# Beacon.net
KiCad netlist of a schematic drawn in EAGLE
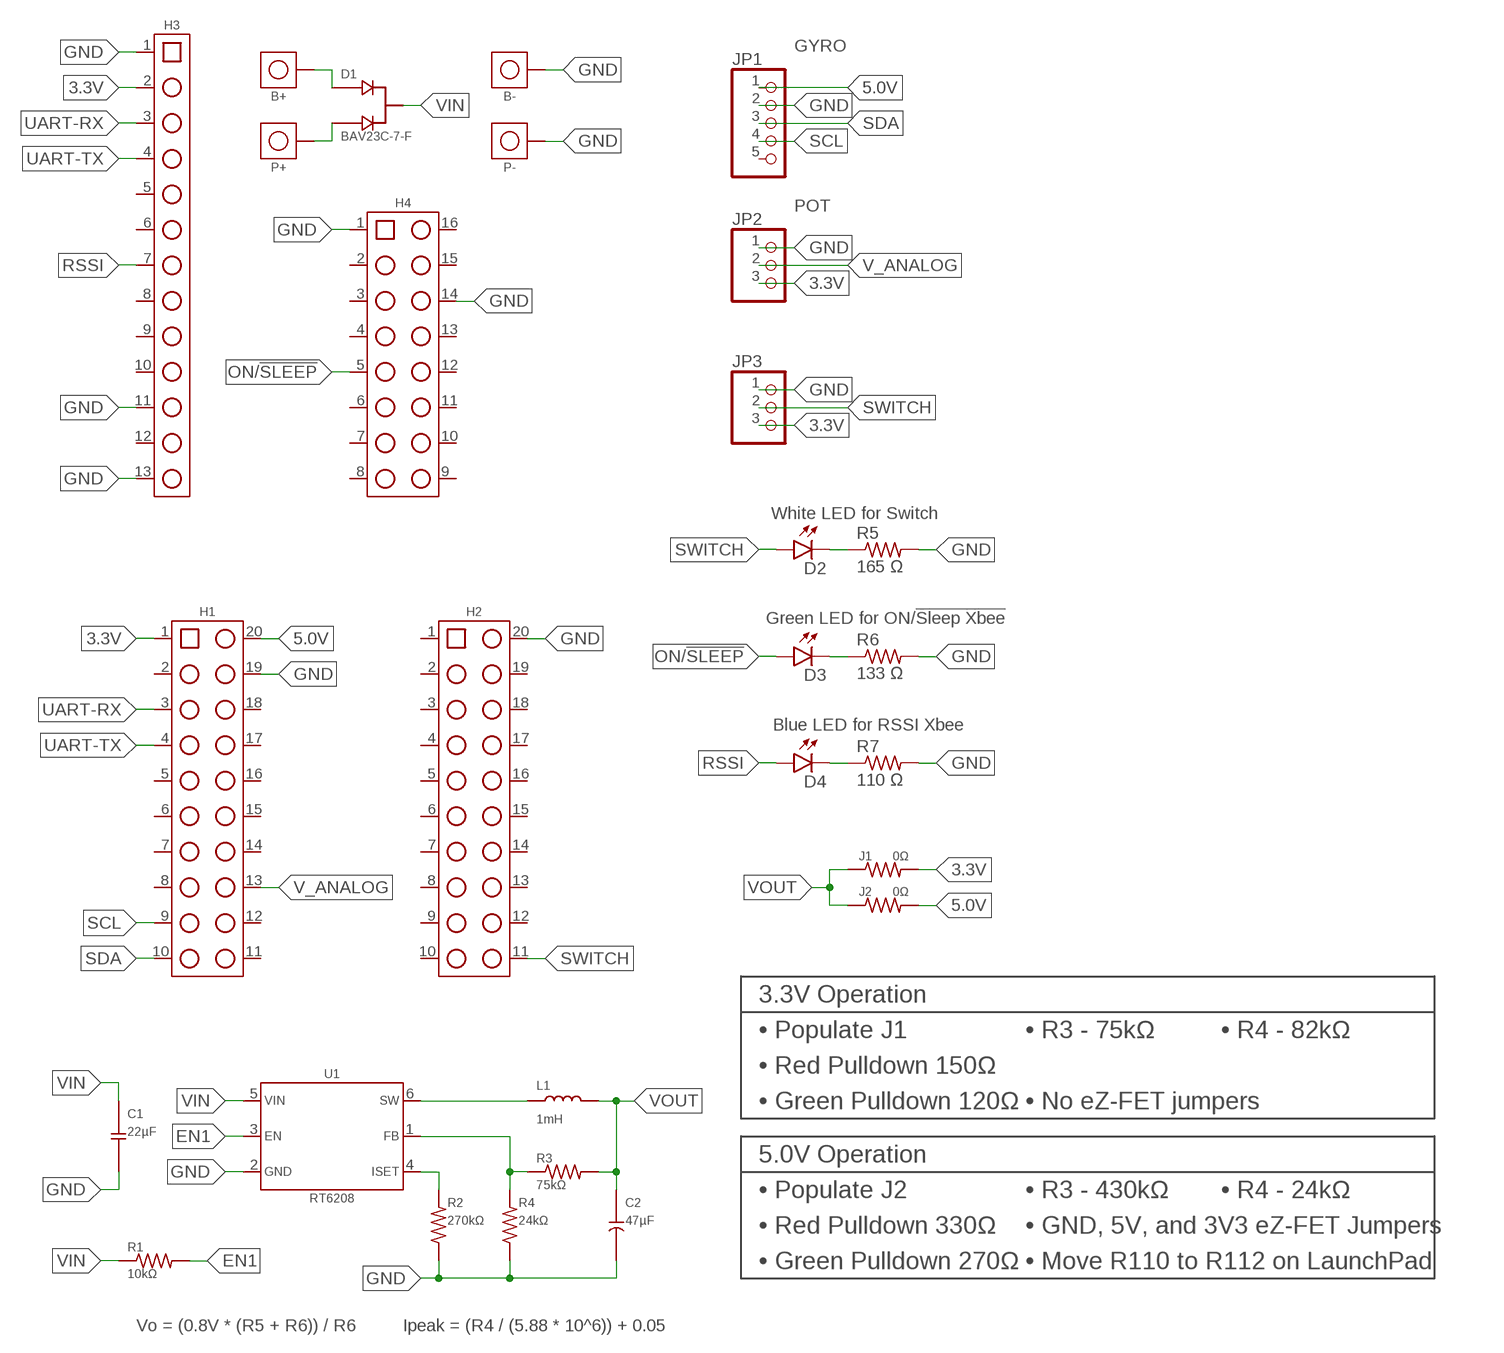
[diagram p0: schematic, sheet 1]

(export (version "E")
  (design (tool "Eeschema 10.0.6"))
  (components
    (comp (ref "B+")
      (value "CON_HEADER-01WTB-24G")
      (footprint "eagle-import:THT_WTB-24G")
      (libsource (lib "eagle-import") (part "CON_HEADER-01WTB-24G"))
    )
    (comp (ref "B-")
      (value "CON_HEADER-01WTB-24G")
      (footprint "eagle-import:THT_WTB-24G")
      (libsource (lib "eagle-import") (part "CON_HEADER-01WTB-24G"))
    )
    (comp (ref "C1")
      (value "22µF")
      (footprint "eagle-import:SMT_1206")
      (libsource (lib "eagle-import") (part "PAS_C1206"))
    )
    (comp (ref "C2")
      (value "47µF")
      (footprint "eagle-import:SMT_CAP-1206")
      (libsource (lib "eagle-import") (part "PAS_C-POLAR"))
    )
    (comp (ref "D1")
      (value "BAV23C-7-F")
      (footprint "eagle-import:SMT_SOT23-3")
      (libsource (lib "eagle-import") (part "SEM_DIODE-PAIR-CC"))
    )
    (comp (ref "D2")
      (value "BEAGLEBONE_BLUE_LED-FKIT-1206")
      (footprint "eagle-import:BEAGLEBONE_BLUE_BEAGLEBONE_BLUE_FKIT-LED-1206")
      (libsource (lib "eagle-import") (part "BEAGLEBONE_BLUE_LED-FKIT-1206"))
    )
    (comp (ref "D3")
      (value "BEAGLEBONE_BLUE_LED-FKIT-1206")
      (footprint "eagle-import:BEAGLEBONE_BLUE_BEAGLEBONE_BLUE_FKIT-LED-1206")
      (libsource (lib "eagle-import") (part "BEAGLEBONE_BLUE_LED-FKIT-1206"))
    )
    (comp (ref "D4")
      (value "BEAGLEBONE_BLUE_LED-FKIT-1206")
      (footprint "eagle-import:BEAGLEBONE_BLUE_BEAGLEBONE_BLUE_FKIT-LED-1206")
      (libsource (lib "eagle-import") (part "BEAGLEBONE_BLUE_LED-FKIT-1206"))
    )
    (comp (ref "H1")
      (value "CON_HEADER-20")
      (footprint "eagle-import:CON_HEADER-0.1_-TH-2×10")
      (libsource (lib "eagle-import") (part "CON_HEADER-20"))
    )
    (comp (ref "H2")
      (value "CON_HEADER-20")
      (footprint "eagle-import:CON_HEADER-0.1_-TH-2×10")
      (libsource (lib "eagle-import") (part "CON_HEADER-20"))
    )
    (comp (ref "H3")
      (value "CON_HEADER-13SM-B")
      (footprint "eagle-import:CON_HEADER-2MM-SM-1×13B")
      (fields (field (name "P1") "1"))
      (libsource (lib "eagle-import") (part "CON_HEADER-13SM-B"))
    )
    (comp (ref "H4")
      (value "CON_HEADER-16SM-B")
      (footprint "eagle-import:CON_HEADER-2MM-SM-1×16B")
      (fields (field (name "P1") "22"))
      (libsource (lib "eagle-import") (part "CON_HEADER-16SM-B"))
    )
    (comp (ref "J1")
      (value "0Ω")
      (footprint "eagle-import:SMT_0603")
      (libsource (lib "eagle-import") (part "PAS_R0603"))
    )
    (comp (ref "J2")
      (value "0Ω")
      (footprint "eagle-import:SMT_0603")
      (libsource (lib "eagle-import") (part "PAS_R0603"))
    )
    (comp (ref "JP1")
      (value "PINHD-1X5")
      (footprint "eagle-import:1X05")
      (libsource (lib "eagle-import") (part "PINHD-1X5"))
    )
    (comp (ref "JP2")
      (value "PINHD-1X3/90")
      (footprint "eagle-import:1X03_90")
      (libsource (lib "eagle-import") (part "PINHD-1X3/90"))
    )
    (comp (ref "JP3")
      (value "PINHD-1X3/90")
      (footprint "eagle-import:1X03_90")
      (libsource (lib "eagle-import") (part "PINHD-1X3/90"))
    )
    (comp (ref "L1")
      (value "1mH")
      (footprint "eagle-import:SMT_1210")
      (libsource (lib "eagle-import") (part "PAS_L1210"))
    )
    (comp (ref "P+")
      (value "CON_HEADER-01WTB-24G")
      (footprint "eagle-import:THT_WTB-24G")
      (libsource (lib "eagle-import") (part "CON_HEADER-01WTB-24G"))
    )
    (comp (ref "P-")
      (value "CON_HEADER-01WTB-24G")
      (footprint "eagle-import:THT_WTB-24G")
      (libsource (lib "eagle-import") (part "CON_HEADER-01WTB-24G"))
    )
    (comp (ref "R1")
      (value "10kΩ")
      (footprint "eagle-import:SMT_0603")
      (libsource (lib "eagle-import") (part "PAS_R0603"))
    )
    (comp (ref "R2")
      (value "270kΩ")
      (footprint "eagle-import:SMT_0603")
      (libsource (lib "eagle-import") (part "PAS_R0603"))
    )
    (comp (ref "R3")
      (value "75kΩ")
      (footprint "eagle-import:SMT_0603")
      (libsource (lib "eagle-import") (part "PAS_R0603"))
    )
    (comp (ref "R4")
      (value "24kΩ")
      (footprint "eagle-import:SMT_0603")
      (libsource (lib "eagle-import") (part "PAS_R0603"))
    )
    (comp (ref "R5")
      (value "165 Ω")
      (footprint "eagle-import:RES_1206")
      (fields
        (field (name "DIGIKEY_PART_NUMBER") "P0.0ETR-ND")
        (field (name "MANUFACTURER") "Panasonic Electronic Components")
        (field (name "MPN") "ERJ-8GEY0R00V")
        (field (name "CREATED_BY") "PCBLayout.com")
      )
      (libsource (lib "eagle-import") (part "ERJ-8GEY0R00V"))
    )
    (comp (ref "R6")
      (value "133 Ω")
      (footprint "eagle-import:RES_1206")
      (fields
        (field (name "DIGIKEY_PART_NUMBER") "P0.0ETR-ND")
        (field (name "MANUFACTURER") "Panasonic Electronic Components")
        (field (name "MPN") "ERJ-8GEY0R00V")
        (field (name "CREATED_BY") "PCBLayout.com")
      )
      (libsource (lib "eagle-import") (part "ERJ-8GEY0R00V"))
    )
    (comp (ref "R7")
      (value "110 Ω")
      (footprint "eagle-import:RES_1206")
      (fields
        (field (name "DIGIKEY_PART_NUMBER") "P0.0ETR-ND")
        (field (name "MANUFACTURER") "Panasonic Electronic Components")
        (field (name "MPN") "ERJ-8GEY0R00V")
        (field (name "CREATED_BY") "PCBLayout.com")
      )
      (libsource (lib "eagle-import") (part "ERJ-8GEY0R00V"))
    )
    (comp (ref "U1")
      (value "RT6208")
      (footprint "eagle-import:SMT_SOT23-6")
      (fields
        (field (name "A") "VIN")
        (field (name "B") "EN")
        (field (name "C") "GND")
        (field (name "D") "ISET")
        (field (name "E") "FB")
        (field (name "F") "SW")
      )
      (libsource (lib "eagle-import") (part "RT6208"))
    )
  )
  (nets
    (net (code "1") (name "/ON{slash}~{SLEEP}") (class "Default")
      (node (ref "D3") (pin "A") (pinfunction "A_A") (pintype "passive"))
      (node (ref "H4") (pin "5") (pinfunction "PIN_5_5") (pintype "passive"))
    )
    (net (code "2") (name "3.3V") (class "Default")
      (node (ref "H1") (pin "1") (pinfunction "PIN_1_1") (pintype "passive"))
      (node (ref "H3") (pin "2") (pinfunction "PIN_2_2") (pintype "passive"))
      (node (ref "J1") (pin "2") (pinfunction "2_2") (pintype "passive"))
      (node (ref "JP2") (pin "3") (pinfunction "3_3") (pintype "passive"))
      (node (ref "JP3") (pin "3") (pinfunction "3_3") (pintype "passive"))
    )
    (net (code "3") (name "5.0V") (class "Default")
      (node (ref "H1") (pin "20") (pinfunction "PIN_20_20") (pintype "passive"))
      (node (ref "J2") (pin "2") (pinfunction "2_2") (pintype "passive"))
      (node (ref "JP1") (pin "1") (pinfunction "1_1") (pintype "passive"))
    )
    (net (code "4") (name "EN1") (class "Default")
      (node (ref "R1") (pin "2") (pinfunction "2_2") (pintype "passive"))
      (node (ref "U1") (pin "3") (pinfunction "B_3") (pintype "passive"))
    )
    (net (code "5") (name "GND") (class "Default")
      (node (ref "B-") (pin "1") (pinfunction "PIN_1_1") (pintype "bidirectional"))
      (node (ref "C1") (pin "1") (pinfunction "1_1") (pintype "passive"))
      (node (ref "C2") (pin "2") (pinfunction "2_2") (pintype "passive"))
      (node (ref "H1") (pin "19") (pinfunction "PIN_19_19") (pintype "passive"))
      (node (ref "H2") (pin "20") (pinfunction "PIN_20_20") (pintype "passive"))
      (node (ref "H3") (pin "1") (pinfunction "PIN_1_1") (pintype "passive"))
      (node (ref "H3") (pin "11") (pinfunction "PIN_11_11") (pintype "passive"))
      (node (ref "H3") (pin "13") (pinfunction "PIN_13_13") (pintype "passive"))
      (node (ref "H4") (pin "1") (pinfunction "PIN_1_1") (pintype "passive"))
      (node (ref "H4") (pin "14") (pinfunction "PIN_14_14") (pintype "passive"))
      (node (ref "JP1") (pin "2") (pinfunction "2_2") (pintype "passive"))
      (node (ref "JP2") (pin "1") (pinfunction "1_1") (pintype "passive"))
      (node (ref "JP3") (pin "1") (pinfunction "1_1") (pintype "passive"))
      (node (ref "P-") (pin "1") (pinfunction "PIN_1_1") (pintype "bidirectional"))
      (node (ref "R2") (pin "1") (pinfunction "1_1") (pintype "passive"))
      (node (ref "R4") (pin "1") (pinfunction "1_1") (pintype "passive"))
      (node (ref "R5") (pin "2") (pinfunction "2_2") (pintype "passive"))
      (node (ref "R6") (pin "2") (pinfunction "2_2") (pintype "passive"))
      (node (ref "R7") (pin "2") (pinfunction "2_2") (pintype "passive"))
      (node (ref "U1") (pin "2") (pinfunction "C_2") (pintype "passive"))
    )
    (net (code "6") (name "Net-(B+-PIN_1)") (class "Default")
      (node (ref "B+") (pin "1") (pinfunction "PIN_1_1") (pintype "bidirectional"))
      (node (ref "D1") (pin "1") (pinfunction "A1_1") (pintype "passive"))
    )
    (net (code "7") (name "Net-(D1-A2)") (class "Default")
      (node (ref "D1") (pin "2") (pinfunction "A2_2") (pintype "passive"))
      (node (ref "P+") (pin "1") (pinfunction "PIN_1_1") (pintype "bidirectional"))
    )
    (net (code "8") (name "Net-(D2-PadC)") (class "Default")
      (node (ref "D2") (pin "C") (pinfunction "C_C") (pintype "passive"))
      (node (ref "R5") (pin "1") (pinfunction "1_1") (pintype "passive"))
    )
    (net (code "9") (name "Net-(D3-PadC)") (class "Default")
      (node (ref "D3") (pin "C") (pinfunction "C_C") (pintype "passive"))
      (node (ref "R6") (pin "1") (pinfunction "1_1") (pintype "passive"))
    )
    (net (code "10") (name "Net-(D4-PadC)") (class "Default")
      (node (ref "D4") (pin "C") (pinfunction "C_C") (pintype "passive"))
      (node (ref "R7") (pin "1") (pinfunction "1_1") (pintype "passive"))
    )
    (net (code "11") (name "Net-(U1-D)") (class "Default")
      (node (ref "R2") (pin "2") (pinfunction "2_2") (pintype "passive"))
      (node (ref "U1") (pin "4") (pinfunction "D_4") (pintype "passive"))
    )
    (net (code "12") (name "Net-(U1-E)") (class "Default")
      (node (ref "R3") (pin "1") (pinfunction "1_1") (pintype "passive"))
      (node (ref "R4") (pin "2") (pinfunction "2_2") (pintype "passive"))
      (node (ref "U1") (pin "1") (pinfunction "E_1") (pintype "passive"))
    )
    (net (code "13") (name "Net-(U1-F)") (class "Default")
      (node (ref "L1") (pin "1") (pinfunction "1_1") (pintype "passive"))
      (node (ref "U1") (pin "6") (pinfunction "F_6") (pintype "passive"))
    )
    (net (code "14") (name "RSSI") (class "Default")
      (node (ref "D4") (pin "A") (pinfunction "A_A") (pintype "passive"))
      (node (ref "H3") (pin "7") (pinfunction "PIN_7_7") (pintype "passive"))
    )
    (net (code "15") (name "SCL") (class "Default")
      (node (ref "H1") (pin "9") (pinfunction "PIN_9_9") (pintype "passive"))
      (node (ref "JP1") (pin "4") (pinfunction "4_4") (pintype "passive"))
    )
    (net (code "16") (name "SDA") (class "Default")
      (node (ref "H1") (pin "10") (pinfunction "PIN_10_10") (pintype "passive"))
      (node (ref "JP1") (pin "3") (pinfunction "3_3") (pintype "passive"))
    )
    (net (code "17") (name "SWITCH") (class "Default")
      (node (ref "D2") (pin "A") (pinfunction "A_A") (pintype "passive"))
      (node (ref "H2") (pin "11") (pinfunction "PIN_11_11") (pintype "passive"))
      (node (ref "JP3") (pin "2") (pinfunction "2_2") (pintype "passive"))
    )
    (net (code "18") (name "UART-RX") (class "Default")
      (node (ref "H1") (pin "3") (pinfunction "PIN_3_3") (pintype "passive"))
      (node (ref "H3") (pin "3") (pinfunction "PIN_3_3") (pintype "passive"))
    )
    (net (code "19") (name "UART-TX") (class "Default")
      (node (ref "H1") (pin "4") (pinfunction "PIN_4_4") (pintype "passive"))
      (node (ref "H3") (pin "4") (pinfunction "PIN_4_4") (pintype "passive"))
    )
    (net (code "20") (name "VIN") (class "Default")
      (node (ref "C1") (pin "2") (pinfunction "2_2") (pintype "passive"))
      (node (ref "D1") (pin "3") (pinfunction "CC_3") (pintype "passive"))
      (node (ref "R1") (pin "1") (pinfunction "1_1") (pintype "passive"))
      (node (ref "U1") (pin "5") (pinfunction "A_5") (pintype "passive"))
    )
    (net (code "21") (name "VOUT") (class "Default")
      (node (ref "C2") (pin "1") (pinfunction "1_1") (pintype "passive"))
      (node (ref "J1") (pin "1") (pinfunction "1_1") (pintype "passive"))
      (node (ref "J2") (pin "1") (pinfunction "1_1") (pintype "passive"))
      (node (ref "L1") (pin "2") (pinfunction "2_2") (pintype "passive"))
      (node (ref "R3") (pin "2") (pinfunction "2_2") (pintype "passive"))
    )
    (net (code "22") (name "V_ANALOG") (class "Default")
      (node (ref "H1") (pin "13") (pinfunction "PIN_13_13") (pintype "passive"))
      (node (ref "JP2") (pin "2") (pinfunction "2_2") (pintype "passive"))
    )
    (net (code "23") (name "unconnected-(H1-PIN_2-Pad2)") (class "Default")
      (node (ref "H1") (pin "2") (pinfunction "PIN_2_2") (pintype "passive"))
    )
    (net (code "24") (name "unconnected-(H1-PIN_5-Pad5)") (class "Default")
      (node (ref "H1") (pin "5") (pinfunction "PIN_5_5") (pintype "passive"))
    )
    (net (code "25") (name "unconnected-(H1-PIN_6-Pad6)") (class "Default")
      (node (ref "H1") (pin "6") (pinfunction "PIN_6_6") (pintype "passive"))
    )
    (net (code "26") (name "unconnected-(H1-PIN_7-Pad7)") (class "Default")
      (node (ref "H1") (pin "7") (pinfunction "PIN_7_7") (pintype "passive"))
    )
    (net (code "27") (name "unconnected-(H1-PIN_8-Pad8)") (class "Default")
      (node (ref "H1") (pin "8") (pinfunction "PIN_8_8") (pintype "passive"))
    )
    (net (code "28") (name "unconnected-(H1-PIN_11-Pad11)") (class "Default")
      (node (ref "H1") (pin "11") (pinfunction "PIN_11_11") (pintype "passive"))
    )
    (net (code "29") (name "unconnected-(H1-PIN_12-Pad12)") (class "Default")
      (node (ref "H1") (pin "12") (pinfunction "PIN_12_12") (pintype "passive"))
    )
    (net (code "30") (name "unconnected-(H1-PIN_14-Pad14)") (class "Default")
      (node (ref "H1") (pin "14") (pinfunction "PIN_14_14") (pintype "passive"))
    )
    (net (code "31") (name "unconnected-(H1-PIN_15-Pad15)") (class "Default")
      (node (ref "H1") (pin "15") (pinfunction "PIN_15_15") (pintype "passive"))
    )
    (net (code "32") (name "unconnected-(H1-PIN_16-Pad16)") (class "Default")
      (node (ref "H1") (pin "16") (pinfunction "PIN_16_16") (pintype "passive"))
    )
    (net (code "33") (name "unconnected-(H1-PIN_17-Pad17)") (class "Default")
      (node (ref "H1") (pin "17") (pinfunction "PIN_17_17") (pintype "passive"))
    )
    (net (code "34") (name "unconnected-(H1-PIN_18-Pad18)") (class "Default")
      (node (ref "H1") (pin "18") (pinfunction "PIN_18_18") (pintype "passive"))
    )
    (net (code "35") (name "unconnected-(H2-PIN_1-Pad1)") (class "Default")
      (node (ref "H2") (pin "1") (pinfunction "PIN_1_1") (pintype "passive"))
    )
    (net (code "36") (name "unconnected-(H2-PIN_2-Pad2)") (class "Default")
      (node (ref "H2") (pin "2") (pinfunction "PIN_2_2") (pintype "passive"))
    )
    (net (code "37") (name "unconnected-(H2-PIN_3-Pad3)") (class "Default")
      (node (ref "H2") (pin "3") (pinfunction "PIN_3_3") (pintype "passive"))
    )
    (net (code "38") (name "unconnected-(H2-PIN_4-Pad4)") (class "Default")
      (node (ref "H2") (pin "4") (pinfunction "PIN_4_4") (pintype "passive"))
    )
    (net (code "39") (name "unconnected-(H2-PIN_5-Pad5)") (class "Default")
      (node (ref "H2") (pin "5") (pinfunction "PIN_5_5") (pintype "passive"))
    )
    (net (code "40") (name "unconnected-(H2-PIN_6-Pad6)") (class "Default")
      (node (ref "H2") (pin "6") (pinfunction "PIN_6_6") (pintype "passive"))
    )
    (net (code "41") (name "unconnected-(H2-PIN_7-Pad7)") (class "Default")
      (node (ref "H2") (pin "7") (pinfunction "PIN_7_7") (pintype "passive"))
    )
    (net (code "42") (name "unconnected-(H2-PIN_8-Pad8)") (class "Default")
      (node (ref "H2") (pin "8") (pinfunction "PIN_8_8") (pintype "passive"))
    )
    (net (code "43") (name "unconnected-(H2-PIN_9-Pad9)") (class "Default")
      (node (ref "H2") (pin "9") (pinfunction "PIN_9_9") (pintype "passive"))
    )
    (net (code "44") (name "unconnected-(H2-PIN_10-Pad10)") (class "Default")
      (node (ref "H2") (pin "10") (pinfunction "PIN_10_10") (pintype "passive"))
    )
    (net (code "45") (name "unconnected-(H2-PIN_12-Pad12)") (class "Default")
      (node (ref "H2") (pin "12") (pinfunction "PIN_12_12") (pintype "passive"))
    )
    (net (code "46") (name "unconnected-(H2-PIN_13-Pad13)") (class "Default")
      (node (ref "H2") (pin "13") (pinfunction "PIN_13_13") (pintype "passive"))
    )
    (net (code "47") (name "unconnected-(H2-PIN_14-Pad14)") (class "Default")
      (node (ref "H2") (pin "14") (pinfunction "PIN_14_14") (pintype "passive"))
    )
    (net (code "48") (name "unconnected-(H2-PIN_15-Pad15)") (class "Default")
      (node (ref "H2") (pin "15") (pinfunction "PIN_15_15") (pintype "passive"))
    )
    (net (code "49") (name "unconnected-(H2-PIN_16-Pad16)") (class "Default")
      (node (ref "H2") (pin "16") (pinfunction "PIN_16_16") (pintype "passive"))
    )
    (net (code "50") (name "unconnected-(H2-PIN_17-Pad17)") (class "Default")
      (node (ref "H2") (pin "17") (pinfunction "PIN_17_17") (pintype "passive"))
    )
    (net (code "51") (name "unconnected-(H2-PIN_18-Pad18)") (class "Default")
      (node (ref "H2") (pin "18") (pinfunction "PIN_18_18") (pintype "passive"))
    )
    (net (code "52") (name "unconnected-(H2-PIN_19-Pad19)") (class "Default")
      (node (ref "H2") (pin "19") (pinfunction "PIN_19_19") (pintype "passive"))
    )
    (net (code "53") (name "unconnected-(H3-PIN_5-Pad5)") (class "Default")
      (node (ref "H3") (pin "5") (pinfunction "PIN_5_5") (pintype "passive"))
    )
    (net (code "54") (name "unconnected-(H3-PIN_6-Pad6)") (class "Default")
      (node (ref "H3") (pin "6") (pinfunction "PIN_6_6") (pintype "passive"))
    )
    (net (code "55") (name "unconnected-(H3-PIN_8-Pad8)") (class "Default")
      (node (ref "H3") (pin "8") (pinfunction "PIN_8_8") (pintype "passive"))
    )
    (net (code "56") (name "unconnected-(H3-PIN_9-Pad9)") (class "Default")
      (node (ref "H3") (pin "9") (pinfunction "PIN_9_9") (pintype "passive"))
    )
    (net (code "57") (name "unconnected-(H3-PIN_10-Pad10)") (class "Default")
      (node (ref "H3") (pin "10") (pinfunction "PIN_10_10") (pintype "passive"))
    )
    (net (code "58") (name "unconnected-(H3-PIN_12-Pad12)") (class "Default")
      (node (ref "H3") (pin "12") (pinfunction "PIN_12_12") (pintype "passive"))
    )
    (net (code "59") (name "unconnected-(H4-PIN_2-Pad2)") (class "Default")
      (node (ref "H4") (pin "2") (pinfunction "PIN_2_2") (pintype "passive"))
    )
    (net (code "60") (name "unconnected-(H4-PIN_3-Pad3)") (class "Default")
      (node (ref "H4") (pin "3") (pinfunction "PIN_3_3") (pintype "passive"))
    )
    (net (code "61") (name "unconnected-(H4-PIN_4-Pad4)") (class "Default")
      (node (ref "H4") (pin "4") (pinfunction "PIN_4_4") (pintype "passive"))
    )
    (net (code "62") (name "unconnected-(H4-PIN_6-Pad6)") (class "Default")
      (node (ref "H4") (pin "6") (pinfunction "PIN_6_6") (pintype "passive"))
    )
    (net (code "63") (name "unconnected-(H4-PIN_7-Pad7)") (class "Default")
      (node (ref "H4") (pin "7") (pinfunction "PIN_7_7") (pintype "passive"))
    )
    (net (code "64") (name "unconnected-(H4-PIN_8-Pad8)") (class "Default")
      (node (ref "H4") (pin "8") (pinfunction "PIN_8_8") (pintype "passive"))
    )
    (net (code "65") (name "unconnected-(H4-PIN_9-Pad9)") (class "Default")
      (node (ref "H4") (pin "9") (pinfunction "PIN_9_9") (pintype "passive"))
    )
    (net (code "66") (name "unconnected-(H4-PIN_10-Pad10)") (class "Default")
      (node (ref "H4") (pin "10") (pinfunction "PIN_10_10") (pintype "passive"))
    )
    (net (code "67") (name "unconnected-(H4-PIN_11-Pad11)") (class "Default")
      (node (ref "H4") (pin "11") (pinfunction "PIN_11_11") (pintype "passive"))
    )
    (net (code "68") (name "unconnected-(H4-PIN_12-Pad12)") (class "Default")
      (node (ref "H4") (pin "12") (pinfunction "PIN_12_12") (pintype "passive"))
    )
    (net (code "69") (name "unconnected-(H4-PIN_13-Pad13)") (class "Default")
      (node (ref "H4") (pin "13") (pinfunction "PIN_13_13") (pintype "passive"))
    )
    (net (code "70") (name "unconnected-(H4-PIN_15-Pad15)") (class "Default")
      (node (ref "H4") (pin "15") (pinfunction "PIN_15_15") (pintype "passive"))
    )
    (net (code "71") (name "unconnected-(H4-PIN_16-Pad16)") (class "Default")
      (node (ref "H4") (pin "16") (pinfunction "PIN_16_16") (pintype "passive"))
    )
    (net (code "72") (name "unconnected-(JP1-Pad5)") (class "Default")
      (node (ref "JP1") (pin "5") (pinfunction "5_5") (pintype "passive"))
    )
  )
)
